# board_NRF24L01_v2.net
KiCad netlist of a schematic drawn in EAGLE
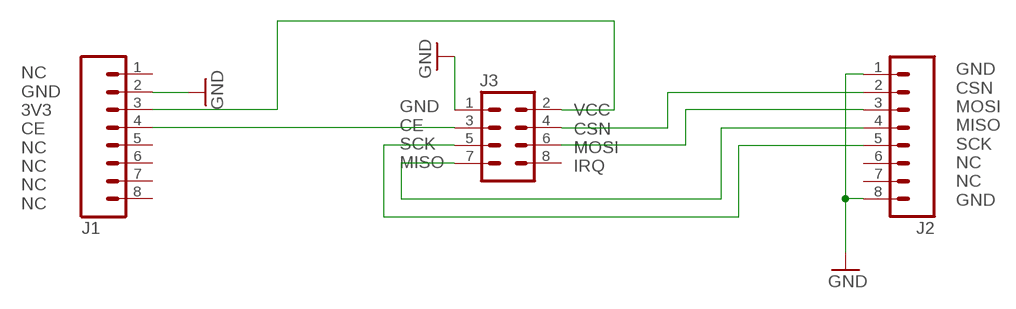
[diagram p0: schematic, sheet 1]

(export (version "E")
  (design (tool "Eeschema 10.0.6"))
  (components
    (comp (ref "J1")
      (value "M08")
      (footprint "eagle-import:1X08_ROUND")
      (libsource (lib "eagle-import") (part "M08"))
    )
    (comp (ref "J2")
      (value "M08")
      (footprint "eagle-import:1X08_ROUND")
      (libsource (lib "eagle-import") (part "M08"))
    )
    (comp (ref "J3")
      (value "M04X2")
      (footprint "eagle-import:2X4")
      (libsource (lib "eagle-import") (part "M04X2"))
    )
  )
  (nets
    (net (code "1") (name "GND") (class "Default")
      (node (ref "J1") (pin "2") (pinfunction "2_2") (pintype "passive"))
      (node (ref "J2") (pin "1") (pinfunction "1_1") (pintype "passive"))
      (node (ref "J2") (pin "8") (pinfunction "8_8") (pintype "passive"))
      (node (ref "J3") (pin "1") (pinfunction "1_1") (pintype "passive"))
    )
    (net (code "2") (name "Net-(J1-Pad3)") (class "Default")
      (node (ref "J1") (pin "3") (pinfunction "3_3") (pintype "passive"))
      (node (ref "J3") (pin "2") (pinfunction "2_2") (pintype "passive"))
    )
    (net (code "3") (name "Net-(J1-Pad4)") (class "Default")
      (node (ref "J1") (pin "4") (pinfunction "4_4") (pintype "passive"))
      (node (ref "J3") (pin "3") (pinfunction "3_3") (pintype "passive"))
    )
    (net (code "4") (name "Net-(J2-Pad2)") (class "Default")
      (node (ref "J2") (pin "2") (pinfunction "2_2") (pintype "passive"))
      (node (ref "J3") (pin "4") (pinfunction "4_4") (pintype "passive"))
    )
    (net (code "5") (name "Net-(J2-Pad3)") (class "Default")
      (node (ref "J2") (pin "3") (pinfunction "3_3") (pintype "passive"))
      (node (ref "J3") (pin "6") (pinfunction "6_6") (pintype "passive"))
    )
    (net (code "6") (name "Net-(J2-Pad4)") (class "Default")
      (node (ref "J2") (pin "4") (pinfunction "4_4") (pintype "passive"))
      (node (ref "J3") (pin "7") (pinfunction "7_7") (pintype "passive"))
    )
    (net (code "7") (name "Net-(J2-Pad5)") (class "Default")
      (node (ref "J2") (pin "5") (pinfunction "5_5") (pintype "passive"))
      (node (ref "J3") (pin "5") (pinfunction "5_5") (pintype "passive"))
    )
    (net (code "8") (name "unconnected-(J1-Pad1)") (class "Default")
      (node (ref "J1") (pin "1") (pinfunction "1_1") (pintype "passive"))
    )
    (net (code "9") (name "unconnected-(J1-Pad5)") (class "Default")
      (node (ref "J1") (pin "5") (pinfunction "5_5") (pintype "passive"))
    )
    (net (code "10") (name "unconnected-(J1-Pad6)") (class "Default")
      (node (ref "J1") (pin "6") (pinfunction "6_6") (pintype "passive"))
    )
    (net (code "11") (name "unconnected-(J1-Pad7)") (class "Default")
      (node (ref "J1") (pin "7") (pinfunction "7_7") (pintype "passive"))
    )
    (net (code "12") (name "unconnected-(J1-Pad8)") (class "Default")
      (node (ref "J1") (pin "8") (pinfunction "8_8") (pintype "passive"))
    )
    (net (code "13") (name "unconnected-(J2-Pad6)") (class "Default")
      (node (ref "J2") (pin "6") (pinfunction "6_6") (pintype "passive"))
    )
    (net (code "14") (name "unconnected-(J2-Pad7)") (class "Default")
      (node (ref "J2") (pin "7") (pinfunction "7_7") (pintype "passive"))
    )
    (net (code "15") (name "unconnected-(J3-Pad8)") (class "Default")
      (node (ref "J3") (pin "8") (pinfunction "8_8") (pintype "passive"))
    )
  )
)
